# Rear_right_lamp_v1.net
KiCad netlist of a schematic drawn in EAGLE
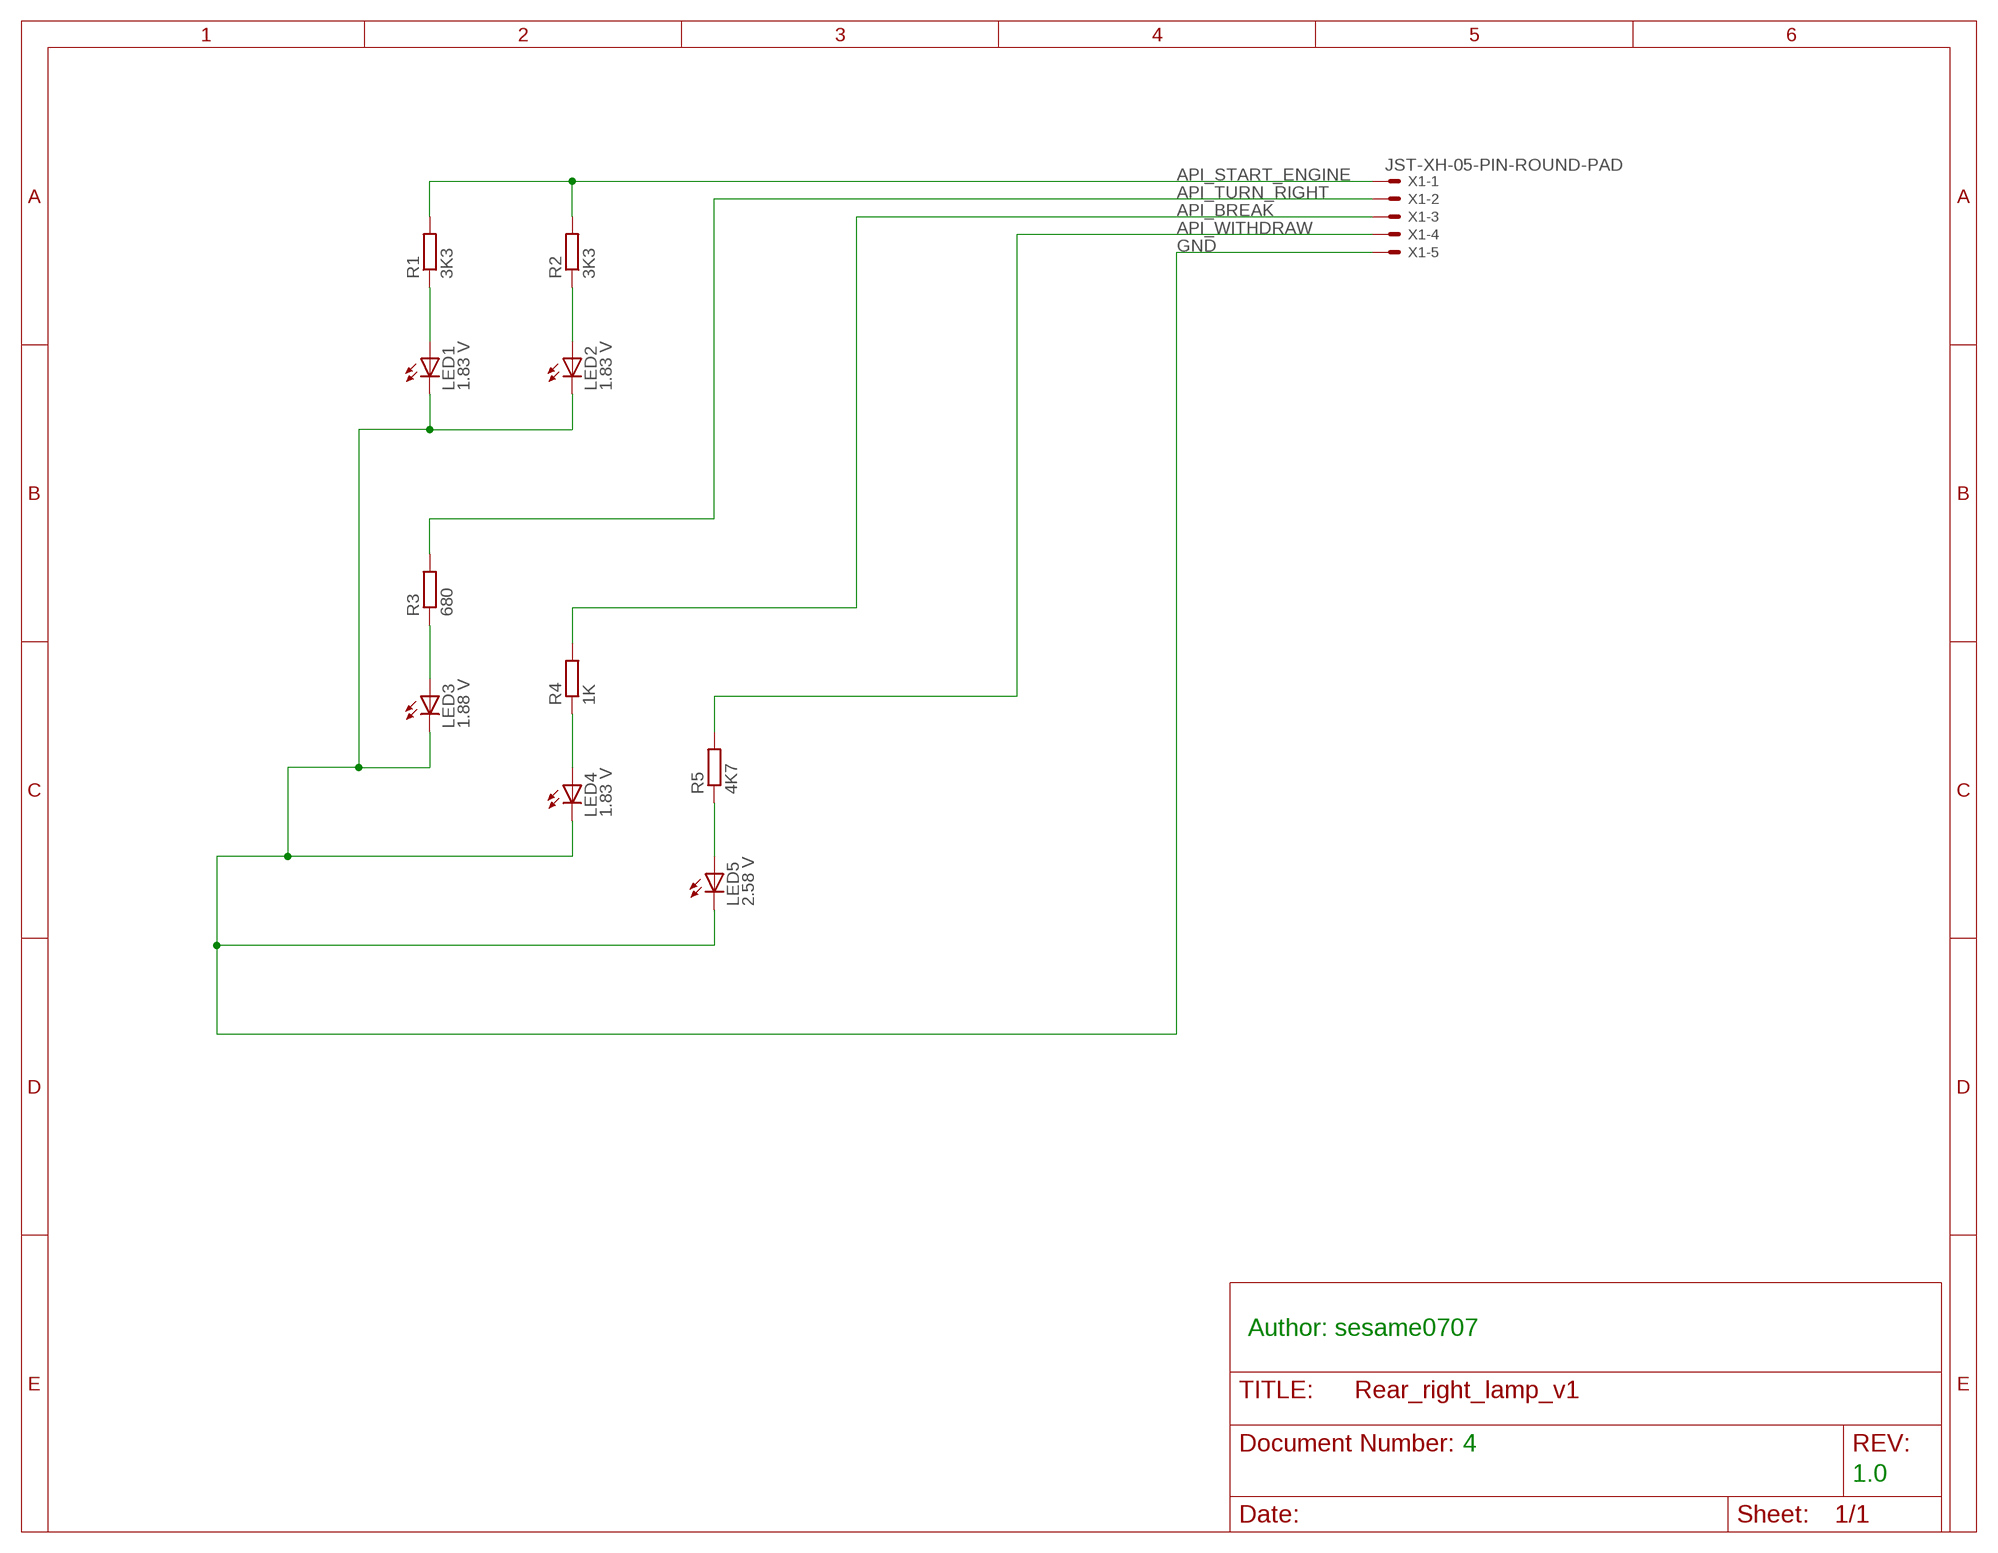
[diagram p0: schematic, sheet 1]

(export (version "E")
  (design (tool "Eeschema 10.0.6"))
  (components
    (comp (ref "LED1")
      (value "1.83 V")
      (footprint "eagle-import:LED5MM")
      (libsource (lib "eagle-import") (part "LED5MM"))
    )
    (comp (ref "LED2")
      (value "1.83 V")
      (footprint "eagle-import:LED5MM")
      (libsource (lib "eagle-import") (part "LED5MM"))
    )
    (comp (ref "LED3")
      (value "1.88 V")
      (footprint "eagle-import:LED5MM")
      (libsource (lib "eagle-import") (part "LED5MM"))
    )
    (comp (ref "LED4")
      (value "1.83 V")
      (footprint "eagle-import:LED5MM")
      (libsource (lib "eagle-import") (part "LED5MM"))
    )
    (comp (ref "LED5")
      (value "2.58 V")
      (footprint "eagle-import:LED5MM")
      (libsource (lib "eagle-import") (part "LED5MM"))
    )
    (comp (ref "R1")
      (value "3K3")
      (footprint "eagle-import:0204V")
      (libsource (lib "eagle-import") (part "R-EU_0204/2V"))
    )
    (comp (ref "R2")
      (value "3K3")
      (footprint "eagle-import:0204V")
      (libsource (lib "eagle-import") (part "R-EU_0204/2V"))
    )
    (comp (ref "R3")
      (value "680")
      (footprint "eagle-import:0204V")
      (libsource (lib "eagle-import") (part "R-EU_0204/2V"))
    )
    (comp (ref "R4")
      (value "1K")
      (footprint "eagle-import:0204V")
      (libsource (lib "eagle-import") (part "R-EU_0204/2V"))
    )
    (comp (ref "R5")
      (value "4K7")
      (footprint "eagle-import:0204V")
      (libsource (lib "eagle-import") (part "R-EU_0204/2V"))
    )
    (comp (ref "X1")
      (value "JST-XH-05-PIN-ROUND-PAD")
      (footprint "eagle-import:JST-XH-05-PACKAGE-ROUND-PAD")
      (libsource (lib "eagle-import") (part "JST-XH-05-PIN-ROUND-PAD"))
    )
  )
  (nets
    (net (code "1") (name "/API_BREAK") (class "Default")
      (node (ref "R4") (pin "2") (pinfunction "2_2") (pintype "passive"))
      (node (ref "X1") (pin "3") (pinfunction "S_3") (pintype "passive"))
    )
    (net (code "2") (name "/API_START_ENGINE") (class "Default")
      (node (ref "R1") (pin "2") (pinfunction "2_2") (pintype "passive"))
      (node (ref "R2") (pin "2") (pinfunction "2_2") (pintype "passive"))
      (node (ref "X1") (pin "1") (pinfunction "S_1") (pintype "passive"))
    )
    (net (code "3") (name "/API_TURN_RIGHT") (class "Default")
      (node (ref "R3") (pin "2") (pinfunction "2_2") (pintype "passive"))
      (node (ref "X1") (pin "2") (pinfunction "S_2") (pintype "passive"))
    )
    (net (code "4") (name "/API_WITHDRAW") (class "Default")
      (node (ref "R5") (pin "2") (pinfunction "2_2") (pintype "passive"))
      (node (ref "X1") (pin "4") (pinfunction "S_4") (pintype "passive"))
    )
    (net (code "5") (name "/GND") (class "Default")
      (node (ref "LED1") (pin "K") (pinfunction "C_K") (pintype "passive"))
      (node (ref "LED2") (pin "K") (pinfunction "C_K") (pintype "passive"))
      (node (ref "LED3") (pin "K") (pinfunction "C_K") (pintype "passive"))
      (node (ref "LED4") (pin "K") (pinfunction "C_K") (pintype "passive"))
      (node (ref "LED5") (pin "K") (pinfunction "C_K") (pintype "passive"))
      (node (ref "X1") (pin "5") (pinfunction "S_5") (pintype "passive"))
    )
    (net (code "6") (name "Net-(LED1-PadA)") (class "Default")
      (node (ref "LED1") (pin "A") (pinfunction "A_A") (pintype "passive"))
      (node (ref "R1") (pin "1") (pinfunction "1_1") (pintype "passive"))
    )
    (net (code "7") (name "Net-(LED2-PadA)") (class "Default")
      (node (ref "LED2") (pin "A") (pinfunction "A_A") (pintype "passive"))
      (node (ref "R2") (pin "1") (pinfunction "1_1") (pintype "passive"))
    )
    (net (code "8") (name "Net-(LED3-PadA)") (class "Default")
      (node (ref "LED3") (pin "A") (pinfunction "A_A") (pintype "passive"))
      (node (ref "R3") (pin "1") (pinfunction "1_1") (pintype "passive"))
    )
    (net (code "9") (name "Net-(LED4-PadA)") (class "Default")
      (node (ref "LED4") (pin "A") (pinfunction "A_A") (pintype "passive"))
      (node (ref "R4") (pin "1") (pinfunction "1_1") (pintype "passive"))
    )
    (net (code "10") (name "Net-(LED5-PadA)") (class "Default")
      (node (ref "LED5") (pin "A") (pinfunction "A_A") (pintype "passive"))
      (node (ref "R5") (pin "1") (pinfunction "1_1") (pintype "passive"))
    )
  )
)
